# st-tag-adapter.net
KiCad netlist of a schematic drawn in EAGLE
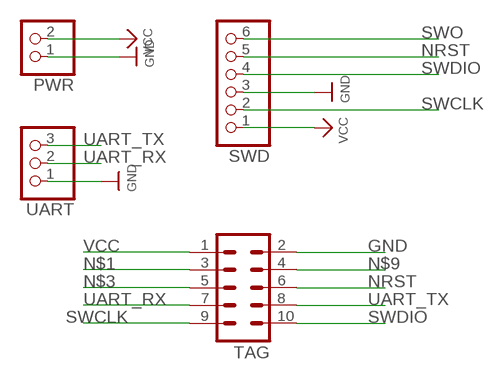
[diagram p0: schematic, sheet 1]

(export (version "E")
  (design (tool "Eeschema 10.0.6"))
  (components
    (comp (ref "PWR")
      (value "HEADER-1X2ROUND")
      (footprint "eagle-import:1X02_ROUND")
      (libsource (lib "eagle-import") (part "HEADER-1X2ROUND"))
    )
    (comp (ref "SWD")
      (value "HEADER-1X6ROUND")
      (footprint "eagle-import:1X06_ROUND")
      (libsource (lib "eagle-import") (part "HEADER-1X6ROUND"))
    )
    (comp (ref "TAG")
      (value "ML10")
      (footprint "eagle-import:ML10")
      (libsource (lib "eagle-import") (part "ML10"))
    )
    (comp (ref "UART")
      (value "HEADER-1X3ROUND")
      (footprint "eagle-import:1X03_ROUND")
      (libsource (lib "eagle-import") (part "HEADER-1X3ROUND"))
    )
  )
  (nets
    (net (code "1") (name "/N$1") (class "Default")
      (node (ref "TAG") (pin "3") (pinfunction "3_3") (pintype "passive"))
    )
    (net (code "2") (name "/N$3") (class "Default")
      (node (ref "TAG") (pin "5") (pinfunction "5_5") (pintype "passive"))
    )
    (net (code "3") (name "/N$9") (class "Default")
      (node (ref "TAG") (pin "4") (pinfunction "4_4") (pintype "passive"))
    )
    (net (code "4") (name "/NRST") (class "Default")
      (node (ref "SWD") (pin "5") (pinfunction "5_5") (pintype "passive"))
      (node (ref "TAG") (pin "6") (pinfunction "6_6") (pintype "passive"))
    )
    (net (code "5") (name "/SWCLK") (class "Default")
      (node (ref "SWD") (pin "2") (pinfunction "2_2") (pintype "passive"))
      (node (ref "TAG") (pin "9") (pinfunction "9_9") (pintype "passive"))
    )
    (net (code "6") (name "/SWDIO") (class "Default")
      (node (ref "SWD") (pin "4") (pinfunction "4_4") (pintype "passive"))
      (node (ref "TAG") (pin "10") (pinfunction "10_10") (pintype "passive"))
    )
    (net (code "7") (name "/SWO") (class "Default")
      (node (ref "SWD") (pin "6") (pinfunction "6_6") (pintype "passive"))
    )
    (net (code "8") (name "/UART_RX") (class "Default")
      (node (ref "TAG") (pin "7") (pinfunction "7_7") (pintype "passive"))
      (node (ref "UART") (pin "2") (pinfunction "2_2") (pintype "passive"))
    )
    (net (code "9") (name "/UART_TX") (class "Default")
      (node (ref "TAG") (pin "8") (pinfunction "8_8") (pintype "passive"))
      (node (ref "UART") (pin "3") (pinfunction "3_3") (pintype "passive"))
    )
    (net (code "10") (name "GND") (class "Default")
      (node (ref "PWR") (pin "1") (pinfunction "1_1") (pintype "passive"))
      (node (ref "SWD") (pin "3") (pinfunction "3_3") (pintype "passive"))
      (node (ref "TAG") (pin "2") (pinfunction "2_2") (pintype "passive"))
      (node (ref "UART") (pin "1") (pinfunction "1_1") (pintype "passive"))
    )
    (net (code "11") (name "VCC") (class "Default")
      (node (ref "PWR") (pin "2") (pinfunction "2_2") (pintype "passive"))
      (node (ref "SWD") (pin "1") (pinfunction "1_1") (pintype "passive"))
      (node (ref "TAG") (pin "1") (pinfunction "1_1") (pintype "passive"))
    )
  )
)
